# power1pDIN5.net
KiCad netlist of a schematic drawn in EAGLE
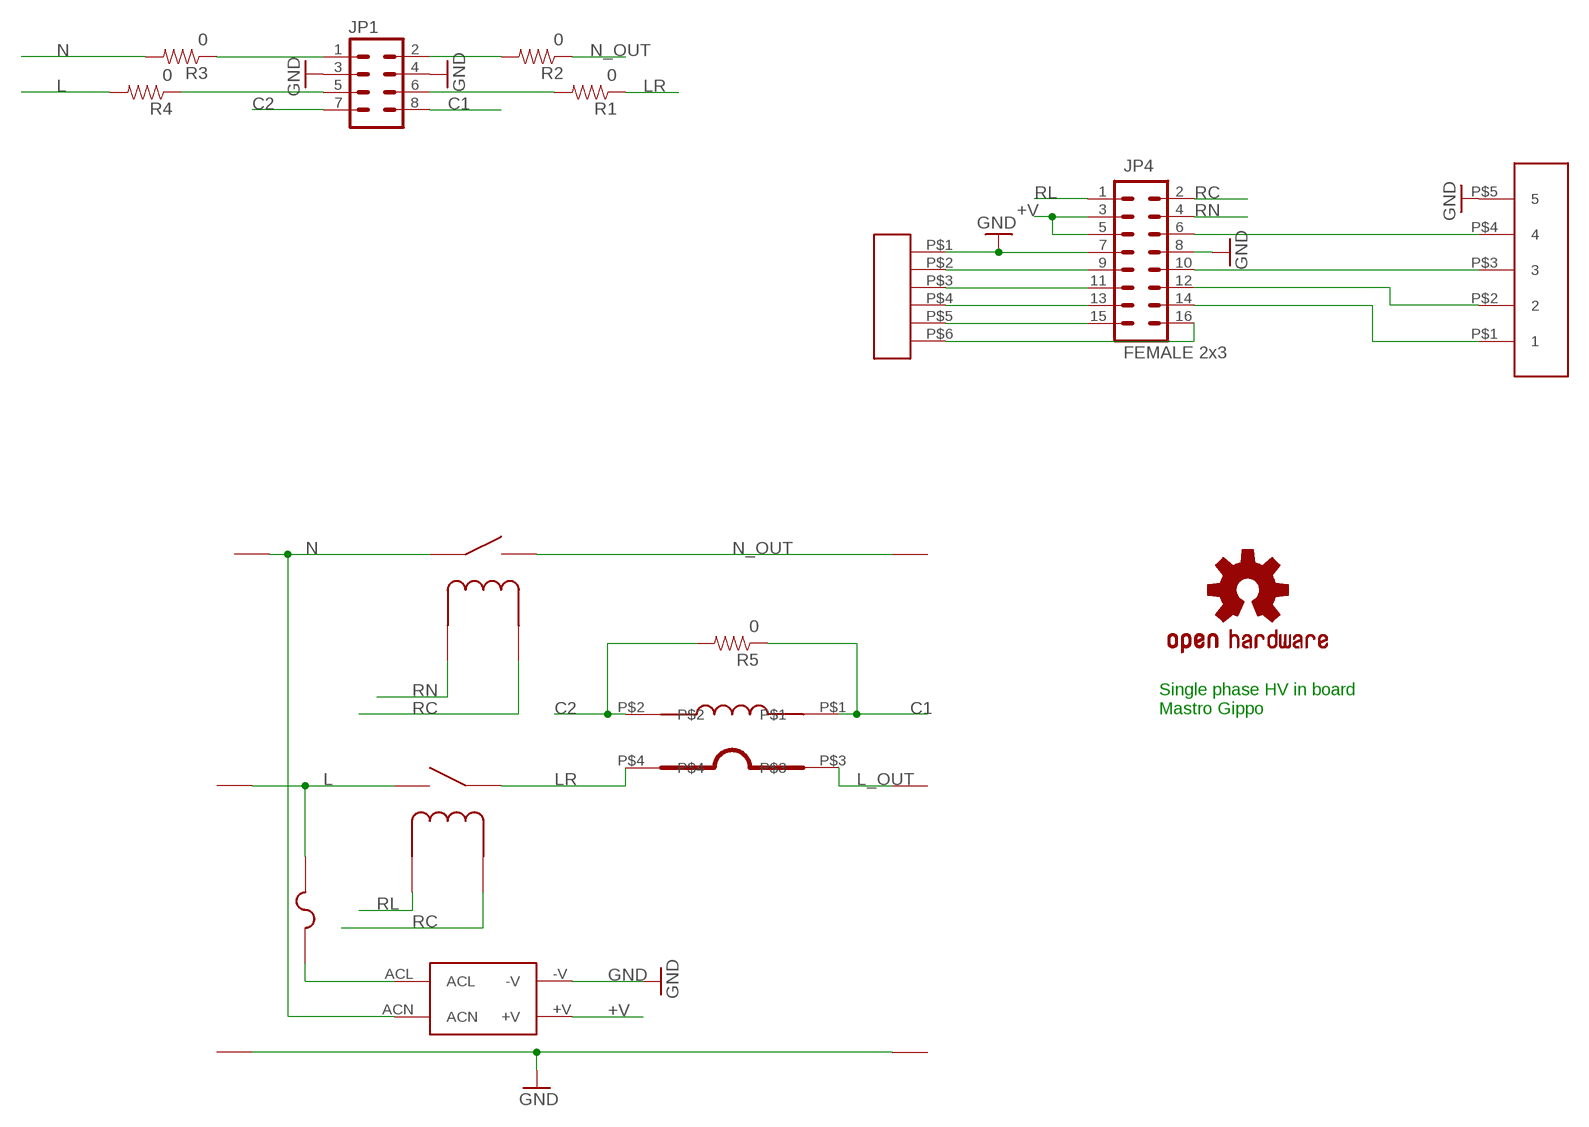
[diagram p0: schematic, sheet 1]

(export (version "E")
  (design (tool "Eeschema 10.0.6"))
  (components
    (comp (ref "JP1")
      (value "M04X2")
      (footprint "eagle-import:2X4")
      (libsource (lib "eagle-import") (part "M04X2"))
    )
    (comp (ref "JP4")
      (value "FEMALE 2x3")
      (footprint "eagle-import:2X8")
      (libsource (lib "eagle-import") (part "M08X2"))
    )
    (comp (ref "R1")
      (value "0")
      (footprint "eagle-import:0805")
      (libsource (lib "eagle-import") (part "RESISTOR0805-RES"))
    )
    (comp (ref "R2")
      (value "0")
      (footprint "eagle-import:0805")
      (libsource (lib "eagle-import") (part "RESISTOR0805-RES"))
    )
    (comp (ref "R3")
      (value "0")
      (footprint "eagle-import:0805")
      (libsource (lib "eagle-import") (part "RESISTOR0805-RES"))
    )
    (comp (ref "R4")
      (value "0")
      (footprint "eagle-import:0805")
      (libsource (lib "eagle-import") (part "RESISTOR0805-RES"))
    )
    (comp (ref "R5")
      (value "0")
      (footprint "eagle-import:0805")
      (libsource (lib "eagle-import") (part "RESISTOR0805-RES"))
    )
    (comp (ref "U$1")
      (value "T9S")
      (footprint "eagle-import:T9SSOLAR")
      (libsource (lib "eagle-import") (part "T9S"))
    )
    (comp (ref "U$2")
      (value "T9S")
      (footprint "eagle-import:T9SSOLAR")
      (libsource (lib "eagle-import") (part "T9S"))
    )
    (comp (ref "U$3")
      (value "PLH5_1")
      (footprint "eagle-import:PLH5")
      (libsource (lib "eagle-import") (part "PLH5_1"))
    )
    (comp (ref "U$4")
      (value "PLH5_1")
      (footprint "eagle-import:PLH5")
      (libsource (lib "eagle-import") (part "PLH5_1"))
    )
    (comp (ref "U$5")
      (value "PLH5_1")
      (footprint "eagle-import:PLH5")
      (libsource (lib "eagle-import") (part "PLH5_1"))
    )
    (comp (ref "U$6")
      (value "PLH5_1")
      (footprint "eagle-import:PLH5")
      (libsource (lib "eagle-import") (part "PLH5_1"))
    )
    (comp (ref "U$7")
      (value "FUSE-0ZRE0008FF1C")
      (footprint "eagle-import:0ZRE0008FF1C")
      (libsource (lib "eagle-import") (part "FUSE-0ZRE0008FF1C"))
    )
    (comp (ref "U$8")
      (value "CSE187L")
      (footprint "eagle-import:CSE187L")
      (libsource (lib "eagle-import") (part "CSE187L"))
    )
    (comp (ref "U$9")
      (value "PLH5_1")
      (footprint "eagle-import:PLH5")
      (libsource (lib "eagle-import") (part "PLH5_1"))
    )
    (comp (ref "U$10")
      (value "PLH5_1")
      (footprint "eagle-import:PLH5")
      (libsource (lib "eagle-import") (part "PLH5_1"))
    )
    (comp (ref "U$11")
      (value "PTSA5")
      (footprint "eagle-import:PTSA5")
      (libsource (lib "eagle-import") (part "PTSA5"))
    )
    (comp (ref "U$12")
      (value "IRM-10-12")
      (footprint "eagle-import:ACDCMEANWELL")
      (libsource (lib "eagle-import") (part "IRM-10-12"))
    )
    (comp (ref "U$13")
      (value "OSHW-LOGOM")
      (footprint "eagle-import:OSHW-LOGO-M")
      (libsource (lib "eagle-import") (part "OSHW-LOGOM"))
    )
    (comp (ref "U$14")
      (value "PTSA6")
      (footprint "eagle-import:PTSA6")
      (libsource (lib "eagle-import") (part "PTSA6"))
    )
  )
  (nets
    (net (code "1") (name "/+V") (class "Default")
      (node (ref "JP4") (pin "3") (pinfunction "3_3") (pintype "passive"))
      (node (ref "JP4") (pin "5") (pinfunction "5_5") (pintype "passive"))
      (node (ref "U$12") (pin "+V") (pinfunction "+V_+V") (pintype "bidirectional"))
    )
    (net (code "2") (name "/C1") (class "Default")
      (node (ref "JP1") (pin "8") (pinfunction "8_8") (pintype "passive"))
      (node (ref "R5") (pin "1") (pinfunction "1_1") (pintype "passive"))
      (node (ref "U$8") (pin "P$1") (pinfunction "P$1_P$1") (pintype "bidirectional"))
    )
    (net (code "3") (name "/C2") (class "Default")
      (node (ref "JP1") (pin "7") (pinfunction "7_7") (pintype "passive"))
      (node (ref "R5") (pin "2") (pinfunction "2_2") (pintype "passive"))
      (node (ref "U$8") (pin "P$2") (pinfunction "P$2_P$2") (pintype "bidirectional"))
    )
    (net (code "4") (name "/L") (class "Default")
      (node (ref "R4") (pin "2") (pinfunction "2_2") (pintype "passive"))
      (node (ref "U$2") (pin "TL1") (pinfunction "TL_TL1") (pintype "bidirectional"))
      (node (ref "U$2") (pin "TL2") (pinfunction "TL_TL2") (pintype "bidirectional"))
      (node (ref "U$4") (pin "P$1") (pinfunction "P$1_P$1") (pintype "bidirectional"))
      (node (ref "U$4") (pin "P$2") (pinfunction "P$1_P$2") (pintype "bidirectional"))
      (node (ref "U$7") (pin "P$2") (pinfunction "2_P$2") (pintype "bidirectional"))
    )
    (net (code "5") (name "/LR") (class "Default")
      (node (ref "R1") (pin "1") (pinfunction "1_1") (pintype "passive"))
      (node (ref "U$2") (pin "TR1") (pinfunction "TR_TR1") (pintype "bidirectional"))
      (node (ref "U$2") (pin "TR2") (pinfunction "TR_TR2") (pintype "bidirectional"))
      (node (ref "U$8") (pin "P$4") (pinfunction "P$4_P$4") (pintype "bidirectional"))
    )
    (net (code "6") (name "/L_OUT") (class "Default")
      (node (ref "U$6") (pin "P$1") (pinfunction "P$1_P$1") (pintype "bidirectional"))
      (node (ref "U$6") (pin "P$2") (pinfunction "P$1_P$2") (pintype "bidirectional"))
      (node (ref "U$8") (pin "P$3") (pinfunction "P$3_P$3") (pintype "bidirectional"))
    )
    (net (code "7") (name "/N") (class "Default")
      (node (ref "R3") (pin "2") (pinfunction "2_2") (pintype "passive"))
      (node (ref "U$1") (pin "TR1") (pinfunction "TR_TR1") (pintype "bidirectional"))
      (node (ref "U$1") (pin "TR2") (pinfunction "TR_TR2") (pintype "bidirectional"))
      (node (ref "U$12") (pin "ACN") (pinfunction "ACN_ACN") (pintype "bidirectional"))
      (node (ref "U$3") (pin "P$1") (pinfunction "P$1_P$1") (pintype "bidirectional"))
      (node (ref "U$3") (pin "P$2") (pinfunction "P$1_P$2") (pintype "bidirectional"))
    )
    (net (code "8") (name "/N_OUT") (class "Default")
      (node (ref "R2") (pin "1") (pinfunction "1_1") (pintype "passive"))
      (node (ref "U$1") (pin "TL1") (pinfunction "TL_TL1") (pintype "bidirectional"))
      (node (ref "U$1") (pin "TL2") (pinfunction "TL_TL2") (pintype "bidirectional"))
      (node (ref "U$5") (pin "P$1") (pinfunction "P$1_P$1") (pintype "bidirectional"))
      (node (ref "U$5") (pin "P$2") (pinfunction "P$1_P$2") (pintype "bidirectional"))
    )
    (net (code "9") (name "/RC") (class "Default")
      (node (ref "JP4") (pin "2") (pinfunction "2_2") (pintype "passive"))
      (node (ref "U$1") (pin "C1") (pinfunction "C1_C1") (pintype "bidirectional"))
      (node (ref "U$2") (pin "C2") (pinfunction "C2_C2") (pintype "bidirectional"))
    )
    (net (code "10") (name "/RL") (class "Default")
      (node (ref "JP4") (pin "1") (pinfunction "1_1") (pintype "passive"))
      (node (ref "U$2") (pin "C1") (pinfunction "C1_C1") (pintype "bidirectional"))
    )
    (net (code "11") (name "/RN") (class "Default")
      (node (ref "JP4") (pin "4") (pinfunction "4_4") (pintype "passive"))
      (node (ref "U$1") (pin "C2") (pinfunction "C2_C2") (pintype "bidirectional"))
    )
    (net (code "12") (name "GND") (class "Default")
      (node (ref "JP1") (pin "3") (pinfunction "3_3") (pintype "passive"))
      (node (ref "JP1") (pin "4") (pinfunction "4_4") (pintype "passive"))
      (node (ref "JP4") (pin "7") (pinfunction "7_7") (pintype "passive"))
      (node (ref "JP4") (pin "8") (pinfunction "8_8") (pintype "passive"))
      (node (ref "U$10") (pin "P$1") (pinfunction "P$1_P$1") (pintype "bidirectional"))
      (node (ref "U$10") (pin "P$2") (pinfunction "P$1_P$2") (pintype "bidirectional"))
      (node (ref "U$11") (pin "P$5") (pinfunction "5_P$5") (pintype "bidirectional"))
      (node (ref "U$12") (pin "-V") (pinfunction "-V_-V") (pintype "bidirectional"))
      (node (ref "U$14") (pin "P$1") (pinfunction "P$1_P$1") (pintype "bidirectional"))
      (node (ref "U$9") (pin "P$1") (pinfunction "P$1_P$1") (pintype "bidirectional"))
      (node (ref "U$9") (pin "P$2") (pinfunction "P$1_P$2") (pintype "bidirectional"))
    )
    (net (code "13") (name "Net-(JP1-Pad1)") (class "Default")
      (node (ref "JP1") (pin "1") (pinfunction "1_1") (pintype "passive"))
      (node (ref "R3") (pin "1") (pinfunction "1_1") (pintype "passive"))
    )
    (net (code "14") (name "Net-(JP1-Pad2)") (class "Default")
      (node (ref "JP1") (pin "2") (pinfunction "2_2") (pintype "passive"))
      (node (ref "R2") (pin "2") (pinfunction "2_2") (pintype "passive"))
    )
    (net (code "15") (name "Net-(JP1-Pad5)") (class "Default")
      (node (ref "JP1") (pin "5") (pinfunction "5_5") (pintype "passive"))
      (node (ref "R4") (pin "1") (pinfunction "1_1") (pintype "passive"))
    )
    (net (code "16") (name "Net-(JP1-Pad6)") (class "Default")
      (node (ref "JP1") (pin "6") (pinfunction "6_6") (pintype "passive"))
      (node (ref "R1") (pin "2") (pinfunction "2_2") (pintype "passive"))
    )
    (net (code "17") (name "Net-(JP4-Pad9)") (class "Default")
      (node (ref "JP4") (pin "9") (pinfunction "9_9") (pintype "passive"))
      (node (ref "U$14") (pin "P$2") (pinfunction "P$2_P$2") (pintype "bidirectional"))
    )
    (net (code "18") (name "Net-(JP4-Pad11)") (class "Default")
      (node (ref "JP4") (pin "11") (pinfunction "11_11") (pintype "passive"))
      (node (ref "U$14") (pin "P$3") (pinfunction "P$3_P$3") (pintype "bidirectional"))
    )
    (net (code "19") (name "Net-(JP4-Pad13)") (class "Default")
      (node (ref "JP4") (pin "13") (pinfunction "13_13") (pintype "passive"))
      (node (ref "U$14") (pin "P$4") (pinfunction "P$4_P$4") (pintype "bidirectional"))
    )
    (net (code "20") (name "Net-(JP4-Pad15)") (class "Default")
      (node (ref "JP4") (pin "15") (pinfunction "15_15") (pintype "passive"))
      (node (ref "U$14") (pin "P$5") (pinfunction "P$5_P$5") (pintype "bidirectional"))
    )
    (net (code "21") (name "Net-(JP4-Pad16)") (class "Default")
      (node (ref "JP4") (pin "16") (pinfunction "16_16") (pintype "passive"))
      (node (ref "U$14") (pin "P$6") (pinfunction "P$6_P$6") (pintype "bidirectional"))
    )
    (net (code "22") (name "Net-(U$7-1)") (class "Default")
      (node (ref "U$12") (pin "ACL") (pinfunction "ACL_ACL") (pintype "bidirectional"))
      (node (ref "U$7") (pin "P$1") (pinfunction "1_P$1") (pintype "bidirectional"))
    )
    (net (code "23") (name "Net-(U$11-1)") (class "Default")
      (node (ref "JP4") (pin "14") (pinfunction "14_14") (pintype "passive"))
      (node (ref "U$11") (pin "P$1") (pinfunction "1_P$1") (pintype "bidirectional"))
    )
    (net (code "24") (name "Net-(U$11-2)") (class "Default")
      (node (ref "JP4") (pin "12") (pinfunction "12_12") (pintype "passive"))
      (node (ref "U$11") (pin "P$2") (pinfunction "2_P$2") (pintype "bidirectional"))
    )
    (net (code "25") (name "Net-(U$11-3)") (class "Default")
      (node (ref "JP4") (pin "10") (pinfunction "10_10") (pintype "passive"))
      (node (ref "U$11") (pin "P$3") (pinfunction "3_P$3") (pintype "bidirectional"))
    )
    (net (code "26") (name "Net-(U$11-4)") (class "Default")
      (node (ref "JP4") (pin "6") (pinfunction "6_6") (pintype "passive"))
      (node (ref "U$11") (pin "P$4") (pinfunction "4_P$4") (pintype "bidirectional"))
    )
  )
)
